# repeater.net
KiCad netlist of a schematic drawn in EasyEDA Pro
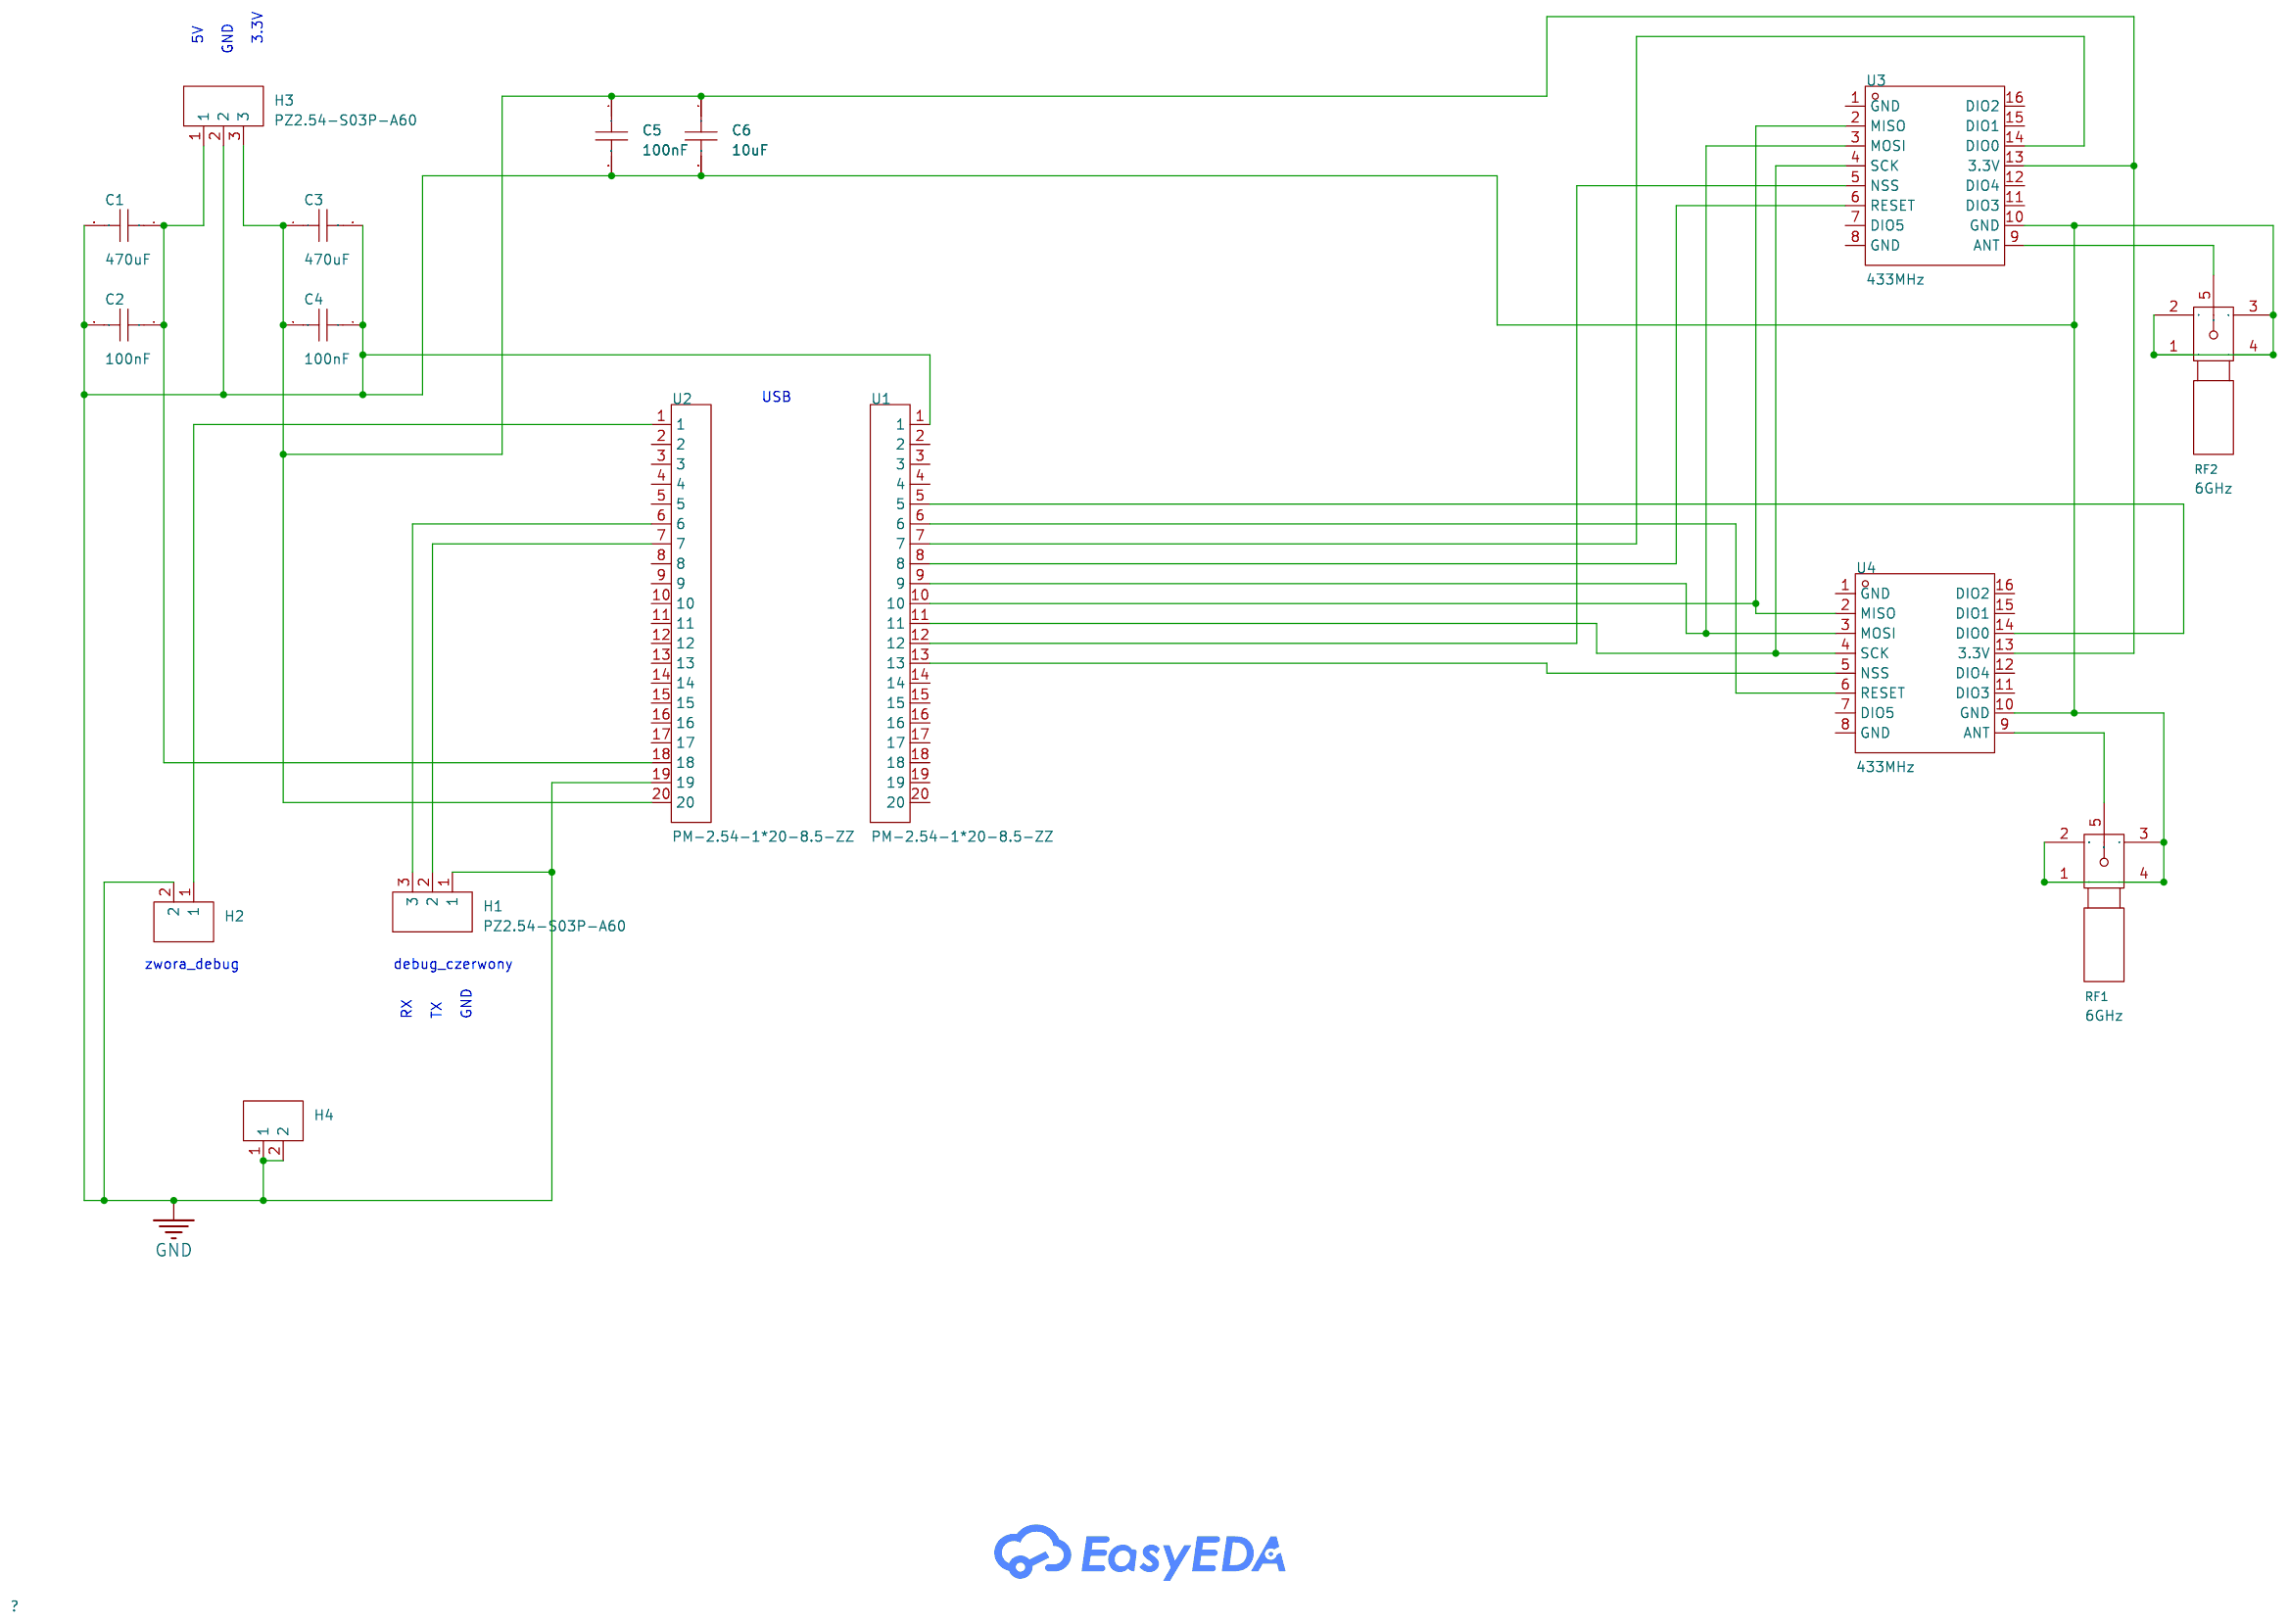
[diagram p0: schematic sheet]

(export (version "E")
  (design (tool "Eeschema 10.0.6"))
  (components
    (comp (ref "C1")
      (value "470uF")
      (footprint "easyedapro:C0603")
      (fields (field (name "Manufacturer Part") "470UF25VG130GF") (field (name "Manufacturer") "Econd(米朗电子)"))
      (libsource (lib "easyedapro") (part "CAP"))
    )
    (comp (ref "C2")
      (value "100nF")
      (footprint "easyedapro:C0603")
      (description "Capacitance:100nF Tolerance:±10% Tolerance:±10% Voltage Rating:50V Temperature Coefficient:X7R")
      (fields
        (field (name "Manufacturer Part") "CC0603KRX7R9BB104")
        (field (name "Manufacturer") "YAGEO(国巨)")
      )
      (libsource (lib "easyedapro") (part "CAP"))
    )
    (comp (ref "C3")
      (value "470uF")
      (footprint "easyedapro:C0603")
      (fields (field (name "Manufacturer Part") "470UF25VG130GF") (field (name "Manufacturer") "Econd(米朗电子)"))
      (libsource (lib "easyedapro") (part "CAP"))
    )
    (comp (ref "C4")
      (value "100nF")
      (footprint "easyedapro:C0603")
      (description "Capacitance:100nF Tolerance:±10% Tolerance:±10% Voltage Rating:50V Temperature Coefficient:X7R")
      (fields
        (field (name "Manufacturer Part") "CC0603KRX7R9BB104")
        (field (name "Manufacturer") "YAGEO(国巨)")
      )
      (libsource (lib "easyedapro") (part "CAP"))
    )
    (comp (ref "C5")
      (value "100nF")
      (footprint "easyedapro:C0603")
      (description "Capacitance:100nF Tolerance:±10% Tolerance:±10% Voltage Rating:50V Temperature Coefficient:X7R")
      (fields
        (field (name "Manufacturer Part") "CC0603KRX7R9BB104")
        (field (name "Manufacturer") "YAGEO(国巨)")
      )
      (libsource (lib "easyedapro") (part "CAP"))
    )
    (comp (ref "C6")
      (value "10uF")
      (footprint "easyedapro:C0603")
      (description "Capacitance:10uF Tolerance:±10% Tolerance:±10% Voltage Rating:10V Temperature Coefficient:X5R")
      (fields
        (field (name "Manufacturer Part") "CL10A106KP8NNNC")
        (field (name "Manufacturer") "SAMSUNG(三星)")
      )
      (libsource (lib "easyedapro") (part "CAP"))
    )
    (comp (ref "H1")
      (value "PZ2.54-S03P-A60")
      (footprint "easyedapro:HDR-TH_3P-P2.54-V-M-B")
      (fields (field (name "Manufacturer") "JXTCONN(聚兴泰)"))
      (libsource (lib "easyedapro") (part "PZ2.54-S03P-A60"))
    )
    (comp (ref "H2")
      (value "PZ2.54-0102P-H25")
      (footprint "easyedapro:HDR-TH_2P-P2.54-V-M_2")
      (fields (field (name "Manufacturer") "JXTCONN(聚兴泰)"))
      (libsource (lib "easyedapro") (part "PZ2.54-0102P-H25"))
    )
    (comp (ref "H3")
      (value "PZ2.54-S03P-A60")
      (footprint "easyedapro:HDR-TH_3P-P2.54-V-M-B")
      (fields (field (name "Manufacturer") "JXTCONN(聚兴泰)"))
      (libsource (lib "easyedapro") (part "PZ2.54-S03P-A60"))
    )
    (comp (ref "H4")
      (value "PZ2.54-0102P-H25")
      (footprint "easyedapro:HDR-TH_2P-P2.54-V-M_2")
      (fields (field (name "Manufacturer") "JXTCONN(聚兴泰)"))
      (libsource (lib "easyedapro") (part "PZ2.54-0102P-H25"))
    )
    (comp (ref "RF1")
      (value "6GHz")
      (footprint "easyedapro:SMA-TH_BWSMA-KE-Z001")
      (fields
        (field (name "Manufacturer Part") "BWSMA-KE-Z001")
        (field (name "Manufacturer") "BAT WIRELESS(蝙蝠无线)")
      )
      (libsource (lib "easyedapro") (part "BWSMA-KE-Z001"))
    )
    (comp (ref "RF2")
      (value "6GHz")
      (footprint "easyedapro:SMA-TH_BWSMA-KE-Z001")
      (fields
        (field (name "Manufacturer Part") "BWSMA-KE-Z001")
        (field (name "Manufacturer") "BAT WIRELESS(蝙蝠无线)")
      )
      (libsource (lib "easyedapro") (part "BWSMA-KE-Z001"))
    )
    (comp (ref "U1")
      (value "PM-2.54-1*20-8.5-ZZ")
      (footprint "easyedapro:HDR-TH_20P-P2.54-V-F-2")
      (fields (field (name "Manufacturer") "BXCONN(宝讯)"))
      (libsource (lib "easyedapro") (part "PM-2.54-1*20-8.5-ZZ"))
    )
    (comp (ref "U2")
      (value "PM-2.54-1*20-8.5-ZZ")
      (footprint "easyedapro:HDR-TH_20P-P2.54-V-F-2")
      (fields (field (name "Manufacturer") "BXCONN(宝讯)"))
      (libsource (lib "easyedapro") (part "PM-2.54-1*20-8.5-ZZ"))
    )
    (comp (ref "U3")
      (value "433MHz")
      (footprint "easyedapro:COMM-SMD_RFM95W")
      (fields
        (field (name "Manufacturer Part") "DL-RFM96-433M")
        (field (name "Manufacturer") "DreamLNK(骏晔科技)")
      )
      (libsource (lib "easyedapro") (part "DL-RFM96-433M"))
    )
    (comp (ref "U4")
      (value "433MHz")
      (footprint "easyedapro:COMM-SMD_RFM95W")
      (fields
        (field (name "Manufacturer Part") "DL-RFM96-433M")
        (field (name "Manufacturer") "DreamLNK(骏晔科技)")
      )
      (libsource (lib "easyedapro") (part "DL-RFM96-433M"))
    )
  )
  (nets
    (net (code "1") (name "GND") (class "Default")
      (node (ref "C1") (pin "2") (pinfunction "2_2") (pintype "input"))
      (node (ref "C2") (pin "2") (pinfunction "2_2") (pintype "input"))
      (node (ref "C3") (pin "2") (pinfunction "2_2") (pintype "input"))
      (node (ref "C4") (pin "1") (pinfunction "1_1") (pintype "input"))
      (node (ref "C5") (pin "2") (pinfunction "2_2") (pintype "input"))
      (node (ref "C6") (pin "2") (pinfunction "2_2") (pintype "input"))
      (node (ref "H1") (pin "1") (pinfunction "1_1") (pintype "unspecified"))
      (node (ref "H2") (pin "2") (pinfunction "2_2") (pintype "unspecified"))
      (node (ref "H3") (pin "2") (pinfunction "2_2") (pintype "unspecified"))
      (node (ref "H4") (pin "1") (pinfunction "1_1") (pintype "unspecified"))
      (node (ref "H4") (pin "2") (pinfunction "2_2") (pintype "unspecified"))
      (node (ref "RF1") (pin "1") (pinfunction "1_1") (pintype "input"))
      (node (ref "RF1") (pin "2") (pinfunction "2_2") (pintype "input"))
      (node (ref "RF1") (pin "3") (pinfunction "3_3") (pintype "input"))
      (node (ref "RF1") (pin "4") (pinfunction "4_4") (pintype "input"))
      (node (ref "RF2") (pin "1") (pinfunction "1_1") (pintype "input"))
      (node (ref "RF2") (pin "2") (pinfunction "2_2") (pintype "input"))
      (node (ref "RF2") (pin "3") (pinfunction "3_3") (pintype "input"))
      (node (ref "RF2") (pin "4") (pinfunction "4_4") (pintype "input"))
      (node (ref "U1") (pin "1") (pinfunction "1_1") (pintype "unspecified"))
      (node (ref "U2") (pin "19") (pinfunction "19_19") (pintype "unspecified"))
      (node (ref "U3") (pin "10") (pinfunction "GND_10") (pintype "unspecified"))
      (node (ref "U4") (pin "10") (pinfunction "GND_10") (pintype "unspecified"))
    )
    (net (code "2") (name "Net-(C1-Pad1)") (class "Default")
      (node (ref "C1") (pin "1") (pinfunction "1_1") (pintype "input"))
      (node (ref "C2") (pin "1") (pinfunction "1_1") (pintype "input"))
      (node (ref "H3") (pin "1") (pinfunction "1_1") (pintype "unspecified"))
      (node (ref "U2") (pin "18") (pinfunction "18_18") (pintype "unspecified"))
    )
    (net (code "3") (name "Net-(H1-Pad2)") (class "Default")
      (node (ref "H1") (pin "2") (pinfunction "2_2") (pintype "unspecified"))
      (node (ref "U2") (pin "7") (pinfunction "7_7") (pintype "unspecified"))
    )
    (net (code "4") (name "Net-(H1-Pad3)") (class "Default")
      (node (ref "H1") (pin "3") (pinfunction "3_3") (pintype "unspecified"))
      (node (ref "U2") (pin "6") (pinfunction "6_6") (pintype "unspecified"))
    )
    (net (code "5") (name "Net-(H2-Pad1)") (class "Default")
      (node (ref "H2") (pin "1") (pinfunction "1_1") (pintype "unspecified"))
      (node (ref "U2") (pin "1") (pinfunction "1_1") (pintype "unspecified"))
    )
    (net (code "6") (name "Net-(U3-3.3V)") (class "Default")
      (node (ref "C3") (pin "1") (pinfunction "1_1") (pintype "input"))
      (node (ref "C4") (pin "2") (pinfunction "2_2") (pintype "input"))
      (node (ref "C5") (pin "1") (pinfunction "1_1") (pintype "input"))
      (node (ref "C6") (pin "1") (pinfunction "1_1") (pintype "input"))
      (node (ref "H3") (pin "3") (pinfunction "3_3") (pintype "unspecified"))
      (node (ref "U2") (pin "20") (pinfunction "20_20") (pintype "unspecified"))
      (node (ref "U3") (pin "13") (pinfunction "3.3V_13") (pintype "unspecified"))
      (node (ref "U4") (pin "13") (pinfunction "3.3V_13") (pintype "unspecified"))
    )
    (net (code "7") (name "Net-(U3-ANT)") (class "Default")
      (node (ref "RF2") (pin "5") (pinfunction "5_5") (pintype "input"))
      (node (ref "U3") (pin "9") (pinfunction "ANT_9") (pintype "unspecified"))
    )
    (net (code "8") (name "Net-(U3-DIO0)") (class "Default")
      (node (ref "U1") (pin "7") (pinfunction "7_7") (pintype "unspecified"))
      (node (ref "U3") (pin "14") (pinfunction "DIO0_14") (pintype "unspecified"))
    )
    (net (code "9") (name "Net-(U3-MISO)") (class "Default")
      (node (ref "U1") (pin "10") (pinfunction "10_10") (pintype "unspecified"))
      (node (ref "U3") (pin "2") (pinfunction "MISO_2") (pintype "unspecified"))
      (node (ref "U4") (pin "2") (pinfunction "MISO_2") (pintype "unspecified"))
    )
    (net (code "10") (name "Net-(U3-MOSI)") (class "Default")
      (node (ref "U1") (pin "9") (pinfunction "9_9") (pintype "unspecified"))
      (node (ref "U3") (pin "3") (pinfunction "MOSI_3") (pintype "unspecified"))
      (node (ref "U4") (pin "3") (pinfunction "MOSI_3") (pintype "unspecified"))
    )
    (net (code "11") (name "Net-(U3-NSS)") (class "Default")
      (node (ref "U1") (pin "12") (pinfunction "12_12") (pintype "unspecified"))
      (node (ref "U3") (pin "5") (pinfunction "NSS_5") (pintype "unspecified"))
    )
    (net (code "12") (name "Net-(U3-RESET)") (class "Default")
      (node (ref "U1") (pin "8") (pinfunction "8_8") (pintype "unspecified"))
      (node (ref "U3") (pin "6") (pinfunction "RESET_6") (pintype "unspecified"))
    )
    (net (code "13") (name "Net-(U3-SCK)") (class "Default")
      (node (ref "U1") (pin "11") (pinfunction "11_11") (pintype "unspecified"))
      (node (ref "U3") (pin "4") (pinfunction "SCK_4") (pintype "unspecified"))
      (node (ref "U4") (pin "4") (pinfunction "SCK_4") (pintype "unspecified"))
    )
    (net (code "14") (name "Net-(U4-ANT)") (class "Default")
      (node (ref "RF1") (pin "5") (pinfunction "5_5") (pintype "input"))
      (node (ref "U4") (pin "9") (pinfunction "ANT_9") (pintype "unspecified"))
    )
    (net (code "15") (name "Net-(U4-DIO0)") (class "Default")
      (node (ref "U1") (pin "5") (pinfunction "5_5") (pintype "unspecified"))
      (node (ref "U4") (pin "14") (pinfunction "DIO0_14") (pintype "unspecified"))
    )
    (net (code "16") (name "Net-(U4-NSS)") (class "Default")
      (node (ref "U1") (pin "13") (pinfunction "13_13") (pintype "unspecified"))
      (node (ref "U4") (pin "5") (pinfunction "NSS_5") (pintype "unspecified"))
    )
    (net (code "17") (name "Net-(U4-RESET)") (class "Default")
      (node (ref "U1") (pin "6") (pinfunction "6_6") (pintype "unspecified"))
      (node (ref "U4") (pin "6") (pinfunction "RESET_6") (pintype "unspecified"))
    )
    (net (code "18") (name "unconnected-(U1-Pad2)") (class "Default")
      (node (ref "U1") (pin "2") (pinfunction "2_2") (pintype "unspecified"))
    )
    (net (code "19") (name "unconnected-(U1-Pad3)") (class "Default")
      (node (ref "U1") (pin "3") (pinfunction "3_3") (pintype "unspecified"))
    )
    (net (code "20") (name "unconnected-(U1-Pad4)") (class "Default")
      (node (ref "U1") (pin "4") (pinfunction "4_4") (pintype "unspecified"))
    )
    (net (code "21") (name "unconnected-(U1-Pad14)") (class "Default")
      (node (ref "U1") (pin "14") (pinfunction "14_14") (pintype "unspecified"))
    )
    (net (code "22") (name "unconnected-(U1-Pad15)") (class "Default")
      (node (ref "U1") (pin "15") (pinfunction "15_15") (pintype "unspecified"))
    )
    (net (code "23") (name "unconnected-(U1-Pad16)") (class "Default")
      (node (ref "U1") (pin "16") (pinfunction "16_16") (pintype "unspecified"))
    )
    (net (code "24") (name "unconnected-(U1-Pad17)") (class "Default")
      (node (ref "U1") (pin "17") (pinfunction "17_17") (pintype "unspecified"))
    )
    (net (code "25") (name "unconnected-(U1-Pad18)") (class "Default")
      (node (ref "U1") (pin "18") (pinfunction "18_18") (pintype "unspecified"))
    )
    (net (code "26") (name "unconnected-(U1-Pad19)") (class "Default")
      (node (ref "U1") (pin "19") (pinfunction "19_19") (pintype "unspecified"))
    )
    (net (code "27") (name "unconnected-(U1-Pad20)") (class "Default")
      (node (ref "U1") (pin "20") (pinfunction "20_20") (pintype "unspecified"))
    )
    (net (code "28") (name "unconnected-(U2-Pad2)") (class "Default")
      (node (ref "U2") (pin "2") (pinfunction "2_2") (pintype "unspecified"))
    )
    (net (code "29") (name "unconnected-(U2-Pad3)") (class "Default")
      (node (ref "U2") (pin "3") (pinfunction "3_3") (pintype "unspecified"))
    )
    (net (code "30") (name "unconnected-(U2-Pad4)") (class "Default")
      (node (ref "U2") (pin "4") (pinfunction "4_4") (pintype "unspecified"))
    )
    (net (code "31") (name "unconnected-(U2-Pad5)") (class "Default")
      (node (ref "U2") (pin "5") (pinfunction "5_5") (pintype "unspecified"))
    )
    (net (code "32") (name "unconnected-(U2-Pad8)") (class "Default")
      (node (ref "U2") (pin "8") (pinfunction "8_8") (pintype "unspecified"))
    )
    (net (code "33") (name "unconnected-(U2-Pad9)") (class "Default")
      (node (ref "U2") (pin "9") (pinfunction "9_9") (pintype "unspecified"))
    )
    (net (code "34") (name "unconnected-(U2-Pad10)") (class "Default")
      (node (ref "U2") (pin "10") (pinfunction "10_10") (pintype "unspecified"))
    )
    (net (code "35") (name "unconnected-(U2-Pad11)") (class "Default")
      (node (ref "U2") (pin "11") (pinfunction "11_11") (pintype "unspecified"))
    )
    (net (code "36") (name "unconnected-(U2-Pad12)") (class "Default")
      (node (ref "U2") (pin "12") (pinfunction "12_12") (pintype "unspecified"))
    )
    (net (code "37") (name "unconnected-(U2-Pad13)") (class "Default")
      (node (ref "U2") (pin "13") (pinfunction "13_13") (pintype "unspecified"))
    )
    (net (code "38") (name "unconnected-(U2-Pad14)") (class "Default")
      (node (ref "U2") (pin "14") (pinfunction "14_14") (pintype "unspecified"))
    )
    (net (code "39") (name "unconnected-(U2-Pad15)") (class "Default")
      (node (ref "U2") (pin "15") (pinfunction "15_15") (pintype "unspecified"))
    )
    (net (code "40") (name "unconnected-(U2-Pad16)") (class "Default")
      (node (ref "U2") (pin "16") (pinfunction "16_16") (pintype "unspecified"))
    )
    (net (code "41") (name "unconnected-(U2-Pad17)") (class "Default")
      (node (ref "U2") (pin "17") (pinfunction "17_17") (pintype "unspecified"))
    )
    (net (code "42") (name "unconnected-(U3-DIO1-Pad15)") (class "Default")
      (node (ref "U3") (pin "15") (pinfunction "DIO1_15") (pintype "unspecified"))
    )
    (net (code "43") (name "unconnected-(U3-DIO2-Pad16)") (class "Default")
      (node (ref "U3") (pin "16") (pinfunction "DIO2_16") (pintype "unspecified"))
    )
    (net (code "44") (name "unconnected-(U3-DIO3-Pad11)") (class "Default")
      (node (ref "U3") (pin "11") (pinfunction "DIO3_11") (pintype "unspecified"))
    )
    (net (code "45") (name "unconnected-(U3-DIO4-Pad12)") (class "Default")
      (node (ref "U3") (pin "12") (pinfunction "DIO4_12") (pintype "unspecified"))
    )
    (net (code "46") (name "unconnected-(U3-DIO5-Pad7)") (class "Default")
      (node (ref "U3") (pin "7") (pinfunction "DIO5_7") (pintype "unspecified"))
    )
    (net (code "47") (name "unconnected-(U3-GND-Pad1)") (class "Default")
      (node (ref "U3") (pin "1") (pinfunction "GND_1") (pintype "unspecified"))
    )
    (net (code "48") (name "unconnected-(U3-GND-Pad8)") (class "Default")
      (node (ref "U3") (pin "8") (pinfunction "GND_8") (pintype "unspecified"))
    )
    (net (code "49") (name "unconnected-(U4-DIO1-Pad15)") (class "Default")
      (node (ref "U4") (pin "15") (pinfunction "DIO1_15") (pintype "unspecified"))
    )
    (net (code "50") (name "unconnected-(U4-DIO2-Pad16)") (class "Default")
      (node (ref "U4") (pin "16") (pinfunction "DIO2_16") (pintype "unspecified"))
    )
    (net (code "51") (name "unconnected-(U4-DIO3-Pad11)") (class "Default")
      (node (ref "U4") (pin "11") (pinfunction "DIO3_11") (pintype "unspecified"))
    )
    (net (code "52") (name "unconnected-(U4-DIO4-Pad12)") (class "Default")
      (node (ref "U4") (pin "12") (pinfunction "DIO4_12") (pintype "unspecified"))
    )
    (net (code "53") (name "unconnected-(U4-DIO5-Pad7)") (class "Default")
      (node (ref "U4") (pin "7") (pinfunction "DIO5_7") (pintype "unspecified"))
    )
    (net (code "54") (name "unconnected-(U4-GND-Pad1)") (class "Default")
      (node (ref "U4") (pin "1") (pinfunction "GND_1") (pintype "unspecified"))
    )
    (net (code "55") (name "unconnected-(U4-GND-Pad8)") (class "Default")
      (node (ref "U4") (pin "8") (pinfunction "GND_8") (pintype "unspecified"))
    )
  )
)
